# Interfaces.net
KiCad netlist of a schematic drawn in Altium Designer
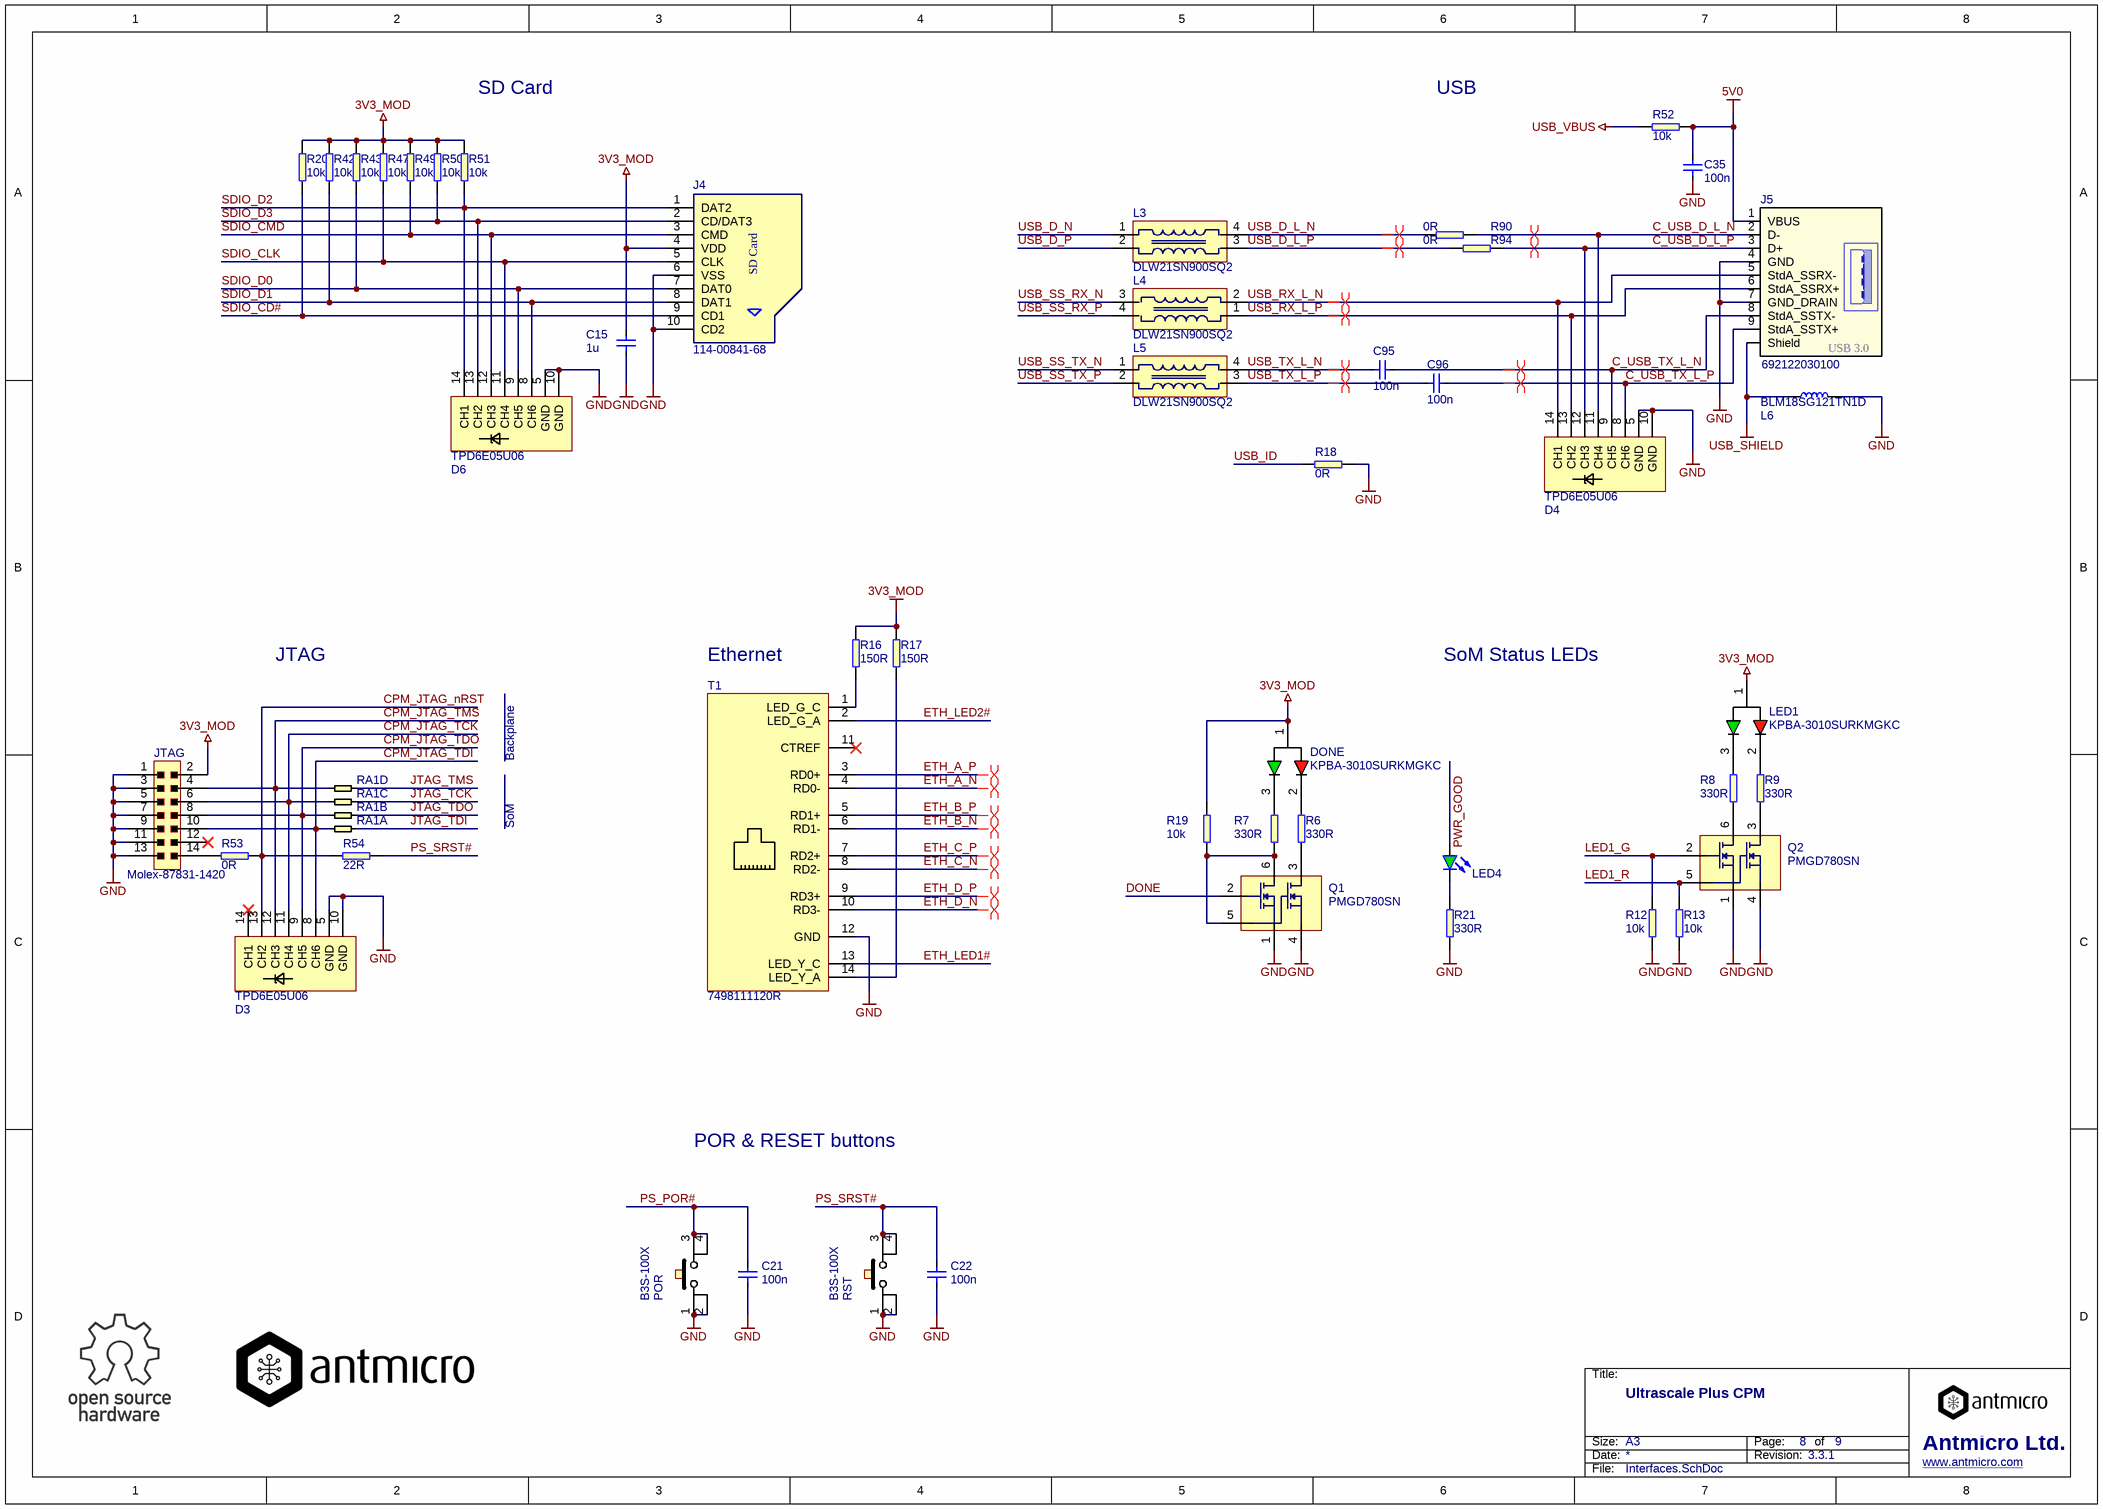
[diagram p0: Interfaces.SchDoc]

(export (version "E")
  (design (tool "Eeschema 10.0.6"))
  (components
    (comp (ref "C15")
      (value "1u")
      (footprint "0603")
      (description "MLCC SMT Capacitor 1uF 0603")
      (fields (field (name "PART NUMBER") "C_1u_0603") (field (name "MANUFACTURER") "MULTICOMP"))
      (libsource (lib "") (part "C_1"))
    )
    (comp (ref "C21")
      (value "100n")
      (footprint "0603")
      (description "MLCC SMT Capacitor 100nF 0603")
      (fields (field (name "PART NUMBER") "C_100n_0603") (field (name "MANUFACTURER") "WALSIN"))
      (libsource (lib "") (part "C_1"))
    )
    (comp (ref "C22")
      (value "100n")
      (footprint "0603")
      (description "MLCC SMT Capacitor 100nF 0603")
      (fields (field (name "PART NUMBER") "C_100n_0603") (field (name "MANUFACTURER") "WALSIN"))
      (libsource (lib "") (part "C_1"))
    )
    (comp (ref "C35")
      (value "100n")
      (footprint "0402")
      (description "MLCC SMT Capacitor 100nF 0402")
      (fields (field (name "PART NUMBER") "C_100n_0402") (field (name "MANUFACTURER") "MULTICOMP"))
      (libsource (lib "US-Plus-CPM") (part "C"))
    )
    (comp (ref "C95")
      (value "100n")
      (footprint "0402")
      (description "MLCC SMT Capacitor 100nF 0402")
      (fields (field (name "PART NUMBER") "C_100n_0402") (field (name "MANUFACTURER") "MULTICOMP"))
      (libsource (lib "US-Plus-CPM") (part "C"))
    )
    (comp (ref "C96")
      (value "100n")
      (footprint "0402")
      (description "MLCC SMT Capacitor 100nF 0402")
      (fields (field (name "PART NUMBER") "C_100n_0402") (field (name "MANUFACTURER") "MULTICOMP"))
      (libsource (lib "US-Plus-CPM") (part "C"))
    )
    (comp (ref "D3")
      (value "TPD6E05U06")
      (footprint "TPD6E05U06_PASS")
      (description "ESD Suppressors 6-CH Pass through layout")
      (fields
        (field (name "PART NUMBER") "TPD6E05U06_PASS")
        (field (name "MANUFACTURER") "Texas Instruments")
      )
      (libsource (lib "US-Plus-CPM") (part "TPD6E05U06"))
    )
    (comp (ref "D4")
      (value "TPD6E05U06")
      (footprint "TPD6E05U06_PASS")
      (description "ESD Suppressors 6-CH Pass through layout")
      (fields
        (field (name "PART NUMBER") "TPD6E05U06_PASS")
        (field (name "MANUFACTURER") "Texas Instruments")
      )
      (libsource (lib "US-Plus-CPM") (part "TPD6E05U06"))
    )
    (comp (ref "D6")
      (value "TPD6E05U06")
      (footprint "TPD6E05U06_PASS")
      (description "ESD Suppressors 6-CH Pass through layout")
      (fields
        (field (name "PART NUMBER") "TPD6E05U06_PASS")
        (field (name "MANUFACTURER") "Texas Instruments")
      )
      (libsource (lib "US-Plus-CPM") (part "TPD6E05U06"))
    )
    (comp (ref "DONE")
      (value "KPBA-3010SURKMGKC")
      (footprint "3010SURKMGKC")
      (description "LED SMD 1104 red/green 3x1mm 140° Lens: transparent")
      (fields (field (name "MANUFACTURER") "Kingbright"))
      (libsource (lib "US-Plus-CPM") (part "3010SURKMGKC"))
    )
    (comp (ref "J4")
      (value "114-00841-68")
      (footprint "114-00841-68")
      (description "Micro SD card holder")
      (fields
        (field (name "PART NUMBER") "AMP-114-00841-68")
        (field (name "MANUFACTURER") "AMPHENOL COMMERCIAL PRODUCTS")
      )
      (libsource (lib "US-Plus-CPM") (part "Micro_SD"))
    )
    (comp (ref "J5")
      (value "692122030100")
      (footprint "WE_692122030100")
      (fields (field (name "PART NUMBER") "WE_692122030100") (field (name "MANUFACTURER") "WURTH ELEKTRONIK"))
      (libsource (lib "US-Plus-CPM") (part "WE_692122030100"))
    )
    (comp (ref "JTAG")
      (value "Molex-87831-1420")
      (footprint "CON-Molex-87831-1420")
      (description "HEADER, SQUARE PIN, M/GRID, 14WAY")
      (fields (field (name "PART NUMBER") "CON-Molex-87831-1420") (field (name "MANUFACTURER") "MOLEX"))
      (libsource (lib "US-Plus-CPM") (part "CON-Molex-87831-1420"))
    )
    (comp (ref "L3")
      (value "DLW21SN900SQ2")
      (footprint "DLW21SN900SQ2")
      (description "Common mode choke")
      (fields (field (name "MANUFACTURER") "MURATA") (field (name "MPN") "DLW21SN900SQ2L"))
      (libsource (lib "") (part "DLW21SN900SQ2_1"))
    )
    (comp (ref "L4")
      (value "DLW21SN900SQ2")
      (footprint "DLW21SN900SQ2")
      (description "Common mode choke")
      (fields (field (name "MANUFACTURER") "MURATA") (field (name "MPN") "DLW21SN900SQ2L"))
      (libsource (lib "US-Plus-CPM") (part "DLW21SN900SQ2"))
    )
    (comp (ref "L5")
      (value "DLW21SN900SQ2")
      (footprint "DLW21SN900SQ2")
      (description "Common mode choke")
      (fields (field (name "MANUFACTURER") "MURATA") (field (name "MPN") "DLW21SN900SQ2L"))
      (libsource (lib "") (part "DLW21SN900SQ2_1"))
    )
    (comp (ref "L6")
      (value "BLM18SG121TN1D")
      (footprint "0603")
      (description "FERRITE BEAD, 0.025OHM, 3A, 0603")
      (fields (field (name "MANUFACTURER") "MURATA"))
      (libsource (lib "US-Plus-CPM") (part "Inductor SMT"))
    )
    (comp (ref "LED1")
      (value "KPBA-3010SURKMGKC")
      (footprint "3010SURKMGKC")
      (description "LED SMD 1104 red/green 3x1mm 140° Lens: transparent")
      (fields (field (name "MANUFACTURER") "Kingbright"))
      (libsource (lib "US-Plus-CPM") (part "3010SURKMGKC"))
    )
    (comp (ref "LED4")
      (value "KPT-1608SGC")
      (footprint "LED0603")
      (description "LED Green 0603 case")
      (fields (field (name "PART NUMBER") "LED_G") (field (name "MANUFACTURER") "KINGBRIGHT"))
      (libsource (lib "US-Plus-CPM") (part "LED"))
    )
    (comp (ref "POR")
      (value "B3S-100X")
      (footprint "B3S-100X")
      (fields
        (field (name "PART NUMBER") "B3S-100X")
        (field (name "MANUFACTURER") "OMRON")
        (field (name "MPN") "B3S-1002")
      )
      (libsource (lib "US-Plus-CPM") (part "TACTILE_SWITCH"))
    )
    (comp (ref "Q1")
      (value "PMGD780SN")
      (footprint "SOT-363")
      (description "60 V, dual N-channel Trench MOSFET")
      (fields (field (name "MANUFACTURER") "NXP") (field (name "MPN") "PMGD780SN,115"))
      (libsource (lib "US-Plus-CPM") (part "PMGD780SN"))
    )
    (comp (ref "Q2")
      (value "PMGD780SN")
      (footprint "SOT-363")
      (description "60 V, dual N-channel Trench MOSFET")
      (fields (field (name "MANUFACTURER") "NXP") (field (name "MPN") "PMGD780SN,115"))
      (libsource (lib "US-Plus-CPM") (part "PMGD780SN"))
    )
    (comp (ref "R6")
      (value "330R")
      (footprint "0603")
      (description "SMT Resistor 330R 0603")
      (fields (field (name "PART NUMBER") "R_330R_0603") (field (name "MANUFACTURER") "BOURNS"))
      (libsource (lib "") (part "R_2"))
    )
    (comp (ref "R7")
      (value "330R")
      (footprint "0603")
      (description "SMT Resistor 330R 0603")
      (fields (field (name "PART NUMBER") "R_330R_0603") (field (name "MANUFACTURER") "BOURNS"))
      (libsource (lib "") (part "R_2"))
    )
    (comp (ref "R8")
      (value "330R")
      (footprint "0402")
      (description "SMT Resistor 0402")
      (fields (field (name "PART NUMBER") "R_330R_0402") (field (name "MANUFACTURER") "MULTICOMP"))
      (libsource (lib "") (part "R_1"))
    )
    (comp (ref "R9")
      (value "330R")
      (footprint "0402")
      (description "SMT Resistor 0402")
      (fields (field (name "PART NUMBER") "R_330R_0402") (field (name "MANUFACTURER") "MULTICOMP"))
      (libsource (lib "") (part "R_1"))
    )
    (comp (ref "R12")
      (value "10k")
      (footprint "0402")
      (description "SMT Resistor 0402")
      (fields (field (name "PART NUMBER") "R_10k_0402") (field (name "MANUFACTURER") "MULTICOMP"))
      (libsource (lib "") (part "R_1"))
    )
    (comp (ref "R13")
      (value "10k")
      (footprint "0402")
      (description "SMT Resistor 0402")
      (fields (field (name "PART NUMBER") "R_10k_0402") (field (name "MANUFACTURER") "MULTICOMP"))
      (libsource (lib "") (part "R_1"))
    )
    (comp (ref "R16")
      (value "150R")
      (footprint "0603")
      (description "SMT Resistor 150R 0603")
      (fields (field (name "PART NUMBER") "R_150R_0603") (field (name "MANUFACTURER") "MULTICOMP"))
      (libsource (lib "") (part "R_1"))
    )
    (comp (ref "R17")
      (value "150R")
      (footprint "0603")
      (description "SMT Resistor 150R 0603")
      (fields (field (name "PART NUMBER") "R_150R_0603") (field (name "MANUFACTURER") "MULTICOMP"))
      (libsource (lib "") (part "R_1"))
    )
    (comp (ref "R18")
      (value "0R")
      (footprint "0603")
      (description "SMT Resistor 0R 0603")
      (fields (field (name "PART NUMBER") "R_0R_0603") (field (name "MANUFACTURER") "BOURNS"))
      (libsource (lib "US-Plus-CPM") (part "R"))
    )
    (comp (ref "R19")
      (value "10k")
      (footprint "0603")
      (description "SMT Resistor 10k 0603")
      (fields (field (name "PART NUMBER") "R_10k_0603") (field (name "MANUFACTURER") "BOURNS"))
      (libsource (lib "") (part "R_1"))
    )
    (comp (ref "R20")
      (value "10k")
      (footprint "0402")
      (description "SMT Resistor 0402")
      (fields (field (name "PART NUMBER") "R_10k_0402") (field (name "MANUFACTURER") "MULTICOMP"))
      (libsource (lib "") (part "R_1"))
    )
    (comp (ref "R21")
      (value "330R")
      (footprint "0603")
      (description "SMT Resistor 330R 0603")
      (fields (field (name "PART NUMBER") "R_330R_0603") (field (name "MANUFACTURER") "BOURNS"))
      (libsource (lib "") (part "R_2"))
    )
    (comp (ref "R42")
      (value "10k")
      (footprint "0402")
      (description "SMT Resistor 0402")
      (fields (field (name "PART NUMBER") "R_10k_0402") (field (name "MANUFACTURER") "MULTICOMP"))
      (libsource (lib "") (part "R_1"))
    )
    (comp (ref "R43")
      (value "10k")
      (footprint "0402")
      (description "SMT Resistor 0402")
      (fields (field (name "PART NUMBER") "R_10k_0402") (field (name "MANUFACTURER") "MULTICOMP"))
      (libsource (lib "") (part "R_1"))
    )
    (comp (ref "R47")
      (value "10k")
      (footprint "0402")
      (description "SMT Resistor 0402")
      (fields (field (name "PART NUMBER") "R_10k_0402") (field (name "MANUFACTURER") "MULTICOMP"))
      (libsource (lib "") (part "R_1"))
    )
    (comp (ref "R49")
      (value "10k")
      (footprint "0402")
      (description "SMT Resistor 0402")
      (fields (field (name "PART NUMBER") "R_10k_0402") (field (name "MANUFACTURER") "MULTICOMP"))
      (libsource (lib "") (part "R_1"))
    )
    (comp (ref "R50")
      (value "10k")
      (footprint "0402")
      (description "SMT Resistor 0402")
      (fields (field (name "PART NUMBER") "R_10k_0402") (field (name "MANUFACTURER") "MULTICOMP"))
      (libsource (lib "") (part "R_1"))
    )
    (comp (ref "R51")
      (value "10k")
      (footprint "0402")
      (description "SMT Resistor 0402")
      (fields (field (name "PART NUMBER") "R_10k_0402") (field (name "MANUFACTURER") "MULTICOMP"))
      (libsource (lib "") (part "R_1"))
    )
    (comp (ref "R52")
      (value "10k")
      (footprint "0603")
      (description "SMT Resistor 10k 0603")
      (fields (field (name "PART NUMBER") "R_10k_0603") (field (name "MANUFACTURER") "BOURNS"))
      (libsource (lib "US-Plus-CPM") (part "R"))
    )
    (comp (ref "R53")
      (value "0R")
      (footprint "0603")
      (description "SMT Resistor 0R 0603")
      (fields (field (name "PART NUMBER") "R_0R_0603") (field (name "MANUFACTURER") "BOURNS"))
      (libsource (lib "US-Plus-CPM") (part "R"))
    )
    (comp (ref "R54")
      (value "22R")
      (footprint "0603")
      (description "SMT Resistor 22R 0603")
      (fields (field (name "PART NUMBER") "R_22R_0603") (field (name "MANUFACTURER") "BOURNS"))
      (libsource (lib "US-Plus-CPM") (part "R"))
    )
    (comp (ref "R90")
      (value "0R")
      (footprint "0402")
      (description "SMT Resistor 0402")
      (fields (field (name "PART NUMBER") "R_0R_0402") (field (name "MANUFACTURER") "MULTICOMP"))
      (libsource (lib "US-Plus-CPM") (part "R"))
    )
    (comp (ref "R94")
      (value "0R")
      (footprint "0402")
      (description "SMT Resistor 0402")
      (fields (field (name "PART NUMBER") "R_0R_0402") (field (name "MANUFACTURER") "MULTICOMP"))
      (libsource (lib "US-Plus-CPM") (part "R"))
    )
    (comp (ref "RA1")
      (value "22R")
      (footprint "RA_1206")
      (description "YAGEO (PHYCOMP)  TC164-JR-0722RL  RESISTOR ARRAY, ARC241 1206 22R")
      (fields
        (field (name "PART NUMBER") "RA-22R-63mW-5%-1206")
        (field (name "MANUFACTURER") "YAGEO (PHYCOMP)")
      )
      (libsource (lib "US-Plus-CPM") (part "Res_array_4"))
    )
    (comp (ref "RST")
      (value "B3S-100X")
      (footprint "B3S-100X")
      (fields
        (field (name "PART NUMBER") "B3S-100X")
        (field (name "MANUFACTURER") "OMRON")
        (field (name "MPN") "B3S-1002")
      )
      (libsource (lib "US-Plus-CPM") (part "TACTILE_SWITCH"))
    )
    (comp (ref "T1")
      (value "7498111120R")
      (footprint "7498111120R")
      (description "LAN transformer 1000Base-T")
      (fields (field (name "PART NUMBER") "WE_7498111120R") (field (name "MANUFACTURER") "WURTH ELEKTRONIK"))
      (libsource (lib "US-Plus-CPM") (part "WE_7498111120R"))
    )
  )
  (nets
    (net (code "1") (name "/CPM_JTAG_TCK") (class "Default")
      (node (ref "D3") (pin "11") (pinfunction "CH4_11") (pintype "passive"))
      (node (ref "JTAG") (pin "6") (pinfunction "6_6") (pintype "passive"))
      (node (ref "RA1") (pin "3") (pinfunction "3_3") (pintype "passive"))
    )
    (net (code "2") (name "/CPM_JTAG_TDI") (class "Default")
      (node (ref "D3") (pin "8") (pinfunction "CH6_8") (pintype "passive"))
      (node (ref "JTAG") (pin "10") (pinfunction "10_10") (pintype "passive"))
      (node (ref "RA1") (pin "1") (pinfunction "1_1") (pintype "passive"))
    )
    (net (code "3") (name "/CPM_JTAG_TDO") (class "Default")
      (node (ref "D3") (pin "9") (pinfunction "CH5_9") (pintype "passive"))
      (node (ref "JTAG") (pin "8") (pinfunction "8_8") (pintype "passive"))
      (node (ref "RA1") (pin "2") (pinfunction "2_2") (pintype "passive"))
    )
    (net (code "4") (name "/CPM_JTAG_TMS") (class "Default")
      (node (ref "D3") (pin "12") (pinfunction "CH3_12") (pintype "passive"))
      (node (ref "JTAG") (pin "4") (pinfunction "4_4") (pintype "passive"))
      (node (ref "RA1") (pin "4") (pinfunction "4_4") (pintype "passive"))
    )
    (net (code "5") (name "/CPM_JTAG_nRST") (class "Default")
      (node (ref "D3") (pin "13") (pinfunction "CH2_13") (pintype "passive"))
      (node (ref "R53") (pin "2") (pintype "passive"))
      (node (ref "R54") (pin "1") (pintype "passive"))
    )
    (net (code "6") (name "/C_USB_D_L_N") (class "Default")
      (node (ref "D4") (pin "11") (pinfunction "CH4_11") (pintype "passive"))
      (node (ref "J5") (pin "2") (pinfunction "D-_2") (pintype "passive"))
      (node (ref "R90") (pin "2") (pintype "passive"))
    )
    (net (code "7") (name "/C_USB_D_L_P") (class "Default")
      (node (ref "D4") (pin "12") (pinfunction "CH3_12") (pintype "passive"))
      (node (ref "J5") (pin "3") (pinfunction "D+_3") (pintype "passive"))
      (node (ref "R94") (pin "2") (pintype "passive"))
    )
    (net (code "8") (name "/C_USB_TX_L_N") (class "Default")
      (node (ref "C95") (pin "2") (pinfunction "2_2") (pintype "passive"))
      (node (ref "D4") (pin "9") (pinfunction "CH5_9") (pintype "passive"))
      (node (ref "J5") (pin "8") (pinfunction "StdA_SSTX-_8") (pintype "passive"))
    )
    (net (code "9") (name "/C_USB_TX_L_P") (class "Default")
      (node (ref "C96") (pin "2") (pinfunction "2_2") (pintype "passive"))
      (node (ref "D4") (pin "8") (pinfunction "CH6_8") (pintype "passive"))
      (node (ref "J5") (pin "9") (pinfunction "StdA_SSTX+_9") (pintype "passive"))
    )
    (net (code "10") (name "/DONE") (class "Default")
      (node (ref "Q1") (pin "2") (pinfunction "G1_2") (pintype "passive"))
    )
    (net (code "11") (name "/ETH_A_N") (class "Default")
      (node (ref "T1") (pin "4") (pinfunction "RD0-_4") (pintype "passive"))
    )
    (net (code "12") (name "/ETH_A_P") (class "Default")
      (node (ref "T1") (pin "3") (pinfunction "RD0+_3") (pintype "passive"))
    )
    (net (code "13") (name "/ETH_B_N") (class "Default")
      (node (ref "T1") (pin "6") (pinfunction "RD1-_6") (pintype "passive"))
    )
    (net (code "14") (name "/ETH_B_P") (class "Default")
      (node (ref "T1") (pin "5") (pinfunction "RD1+_5") (pintype "passive"))
    )
    (net (code "15") (name "/ETH_C_N") (class "Default")
      (node (ref "T1") (pin "8") (pinfunction "RD2-_8") (pintype "passive"))
    )
    (net (code "16") (name "/ETH_C_P") (class "Default")
      (node (ref "T1") (pin "7") (pinfunction "RD2+_7") (pintype "passive"))
    )
    (net (code "17") (name "/ETH_D_N") (class "Default")
      (node (ref "T1") (pin "10") (pinfunction "RD3-_10") (pintype "passive"))
    )
    (net (code "18") (name "/ETH_D_P") (class "Default")
      (node (ref "T1") (pin "9") (pinfunction "RD3+_9") (pintype "passive"))
    )
    (net (code "19") (name "/ETH_LED1#") (class "Default")
      (node (ref "T1") (pin "13") (pinfunction "LED_Y_C_13") (pintype "passive"))
    )
    (net (code "20") (name "/ETH_LED2#") (class "Default")
      (node (ref "T1") (pin "2") (pinfunction "LED_G_A_2") (pintype "passive"))
    )
    (net (code "21") (name "/JTAG_TCK") (class "Default")
      (node (ref "RA1") (pin "7") (pinfunction "7_7") (pintype "passive"))
    )
    (net (code "22") (name "/JTAG_TDI") (class "Default")
      (node (ref "RA1") (pin "5") (pinfunction "5_5") (pintype "passive"))
    )
    (net (code "23") (name "/JTAG_TDO") (class "Default")
      (node (ref "RA1") (pin "6") (pinfunction "6_6") (pintype "passive"))
    )
    (net (code "24") (name "/JTAG_TMS") (class "Default")
      (node (ref "RA1") (pin "8") (pinfunction "8_8") (pintype "passive"))
    )
    (net (code "25") (name "/LED1_G") (class "Default")
      (node (ref "Q2") (pin "2") (pinfunction "G1_2") (pintype "passive"))
      (node (ref "R12") (pin "2") (pintype "passive"))
    )
    (net (code "26") (name "/LED1_R") (class "Default")
      (node (ref "Q2") (pin "5") (pinfunction "G2_5") (pintype "passive"))
      (node (ref "R13") (pin "2") (pintype "passive"))
    )
    (net (code "27") (name "/PS_POR#") (class "Default")
      (node (ref "C21") (pin "2") (pinfunction "2_2") (pintype "passive"))
      (node (ref "POR") (pin "3") (pinfunction "3_3") (pintype "passive"))
      (node (ref "POR") (pin "4") (pinfunction "4_4") (pintype "passive"))
    )
    (net (code "28") (name "/PS_SRST#") (class "Default")
      (node (ref "C22") (pin "2") (pinfunction "2_2") (pintype "passive"))
      (node (ref "R54") (pin "2") (pintype "passive"))
      (node (ref "RST") (pin "3") (pinfunction "3_3") (pintype "passive"))
      (node (ref "RST") (pin "4") (pinfunction "4_4") (pintype "passive"))
    )
    (net (code "29") (name "/PWR_GOOD") (class "Default")
      (node (ref "LED4") (pin "A") (pinfunction "A_A") (pintype "passive"))
    )
    (net (code "30") (name "/SDIO_CD#") (class "Default")
      (node (ref "J4") (pin "9") (pinfunction "CD1_9") (pintype "passive"))
      (node (ref "R20") (pin "1") (pintype "passive"))
    )
    (net (code "31") (name "/SDIO_CLK") (class "Default")
      (node (ref "D6") (pin "11") (pinfunction "CH4_11") (pintype "passive"))
      (node (ref "J4") (pin "5") (pinfunction "CLK_5") (pintype "passive"))
      (node (ref "R47") (pin "1") (pintype "passive"))
    )
    (net (code "32") (name "/SDIO_CMD") (class "Default")
      (node (ref "D6") (pin "12") (pinfunction "CH3_12") (pintype "passive"))
      (node (ref "J4") (pin "3") (pinfunction "CMD_3") (pintype "passive"))
      (node (ref "R49") (pin "1") (pintype "passive"))
    )
    (net (code "33") (name "/SDIO_D0") (class "Default")
      (node (ref "D6") (pin "9") (pinfunction "CH5_9") (pintype "passive"))
      (node (ref "J4") (pin "7") (pinfunction "DAT0_7") (pintype "passive"))
      (node (ref "R43") (pin "1") (pintype "passive"))
    )
    (net (code "34") (name "/SDIO_D1") (class "Default")
      (node (ref "D6") (pin "8") (pinfunction "CH6_8") (pintype "passive"))
      (node (ref "J4") (pin "8") (pinfunction "DAT1_8") (pintype "passive"))
      (node (ref "R42") (pin "1") (pintype "passive"))
    )
    (net (code "35") (name "/SDIO_D2") (class "Default")
      (node (ref "D6") (pin "14") (pinfunction "CH1_14") (pintype "passive"))
      (node (ref "J4") (pin "1") (pinfunction "DAT2_1") (pintype "passive"))
      (node (ref "R51") (pin "1") (pintype "passive"))
    )
    (net (code "36") (name "/SDIO_D3") (class "Default")
      (node (ref "D6") (pin "13") (pinfunction "CH2_13") (pintype "passive"))
      (node (ref "J4") (pin "2") (pinfunction "CD/DAT3_2") (pintype "passive"))
      (node (ref "R50") (pin "1") (pintype "passive"))
    )
    (net (code "37") (name "/USB_D_L_N") (class "Default")
      (node (ref "L3") (pin "4") (pinfunction "4_4") (pintype "passive"))
      (node (ref "R90") (pin "1") (pintype "passive"))
    )
    (net (code "38") (name "/USB_D_L_P") (class "Default")
      (node (ref "L3") (pin "3") (pinfunction "3_3") (pintype "passive"))
      (node (ref "R94") (pin "1") (pintype "passive"))
    )
    (net (code "39") (name "/USB_D_N") (class "Default")
      (node (ref "L3") (pin "1") (pinfunction "1_1") (pintype "passive"))
    )
    (net (code "40") (name "/USB_D_P") (class "Default")
      (node (ref "L3") (pin "2") (pinfunction "2_2") (pintype "passive"))
    )
    (net (code "41") (name "/USB_ID") (class "Default") (node (ref "R18") (pin "1") (pintype "passive")))
    (net (code "42") (name "/USB_RX_L_N") (class "Default")
      (node (ref "D4") (pin "14") (pinfunction "CH1_14") (pintype "passive"))
      (node (ref "J5") (pin "5") (pinfunction "StdA_SSRX-_5") (pintype "passive"))
      (node (ref "L4") (pin "2") (pinfunction "2_2") (pintype "passive"))
    )
    (net (code "43") (name "/USB_RX_L_P") (class "Default")
      (node (ref "D4") (pin "13") (pinfunction "CH2_13") (pintype "passive"))
      (node (ref "J5") (pin "6") (pinfunction "StdA_SSRX+_6") (pintype "passive"))
      (node (ref "L4") (pin "1") (pinfunction "1_1") (pintype "passive"))
    )
    (net (code "44") (name "/USB_SS_RX_N") (class "Default")
      (node (ref "L4") (pin "3") (pinfunction "3_3") (pintype "passive"))
    )
    (net (code "45") (name "/USB_SS_RX_P") (class "Default")
      (node (ref "L4") (pin "4") (pinfunction "4_4") (pintype "passive"))
    )
    (net (code "46") (name "/USB_SS_TX_N") (class "Default")
      (node (ref "L5") (pin "1") (pinfunction "1_1") (pintype "passive"))
    )
    (net (code "47") (name "/USB_SS_TX_P") (class "Default")
      (node (ref "L5") (pin "2") (pinfunction "2_2") (pintype "passive"))
    )
    (net (code "48") (name "/USB_TX_L_N") (class "Default")
      (node (ref "C95") (pin "1") (pinfunction "1_1") (pintype "passive"))
      (node (ref "L5") (pin "4") (pinfunction "4_4") (pintype "passive"))
    )
    (net (code "49") (name "/USB_TX_L_P") (class "Default")
      (node (ref "C96") (pin "1") (pinfunction "1_1") (pintype "passive"))
      (node (ref "L5") (pin "3") (pinfunction "3_3") (pintype "passive"))
    )
    (net (code "50") (name "3V3_MOD") (class "Default")
      (node (ref "C15") (pin "2") (pinfunction "2_2") (pintype "passive"))
      (node (ref "DONE") (pin "1") (pinfunction "CA_1") (pintype "passive"))
      (node (ref "J4") (pin "4") (pinfunction "VDD_4") (pintype "passive"))
      (node (ref "JTAG") (pin "2") (pinfunction "2_2") (pintype "passive"))
      (node (ref "LED1") (pin "1") (pinfunction "CA_1") (pintype "passive"))
      (node (ref "R16") (pin "2") (pintype "passive"))
      (node (ref "R17") (pin "2") (pintype "passive"))
      (node (ref "R19") (pin "2") (pintype "passive"))
      (node (ref "R20") (pin "2") (pintype "passive"))
      (node (ref "R42") (pin "2") (pintype "passive"))
      (node (ref "R43") (pin "2") (pintype "passive"))
      (node (ref "R47") (pin "2") (pintype "passive"))
      (node (ref "R49") (pin "2") (pintype "passive"))
      (node (ref "R50") (pin "2") (pintype "passive"))
      (node (ref "R51") (pin "2") (pintype "passive"))
    )
    (net (code "51") (name "5V0") (class "Default")
      (node (ref "C35") (pin "2") (pinfunction "2_2") (pintype "passive"))
      (node (ref "J5") (pin "1") (pinfunction "VBUS_1") (pintype "passive"))
      (node (ref "R52") (pin "2") (pintype "passive"))
    )
    (net (code "52") (name "GND") (class "Default")
      (node (ref "C15") (pin "1") (pinfunction "1_1") (pintype "passive"))
      (node (ref "C21") (pin "1") (pinfunction "1_1") (pintype "passive"))
      (node (ref "C22") (pin "1") (pinfunction "1_1") (pintype "passive"))
      (node (ref "C35") (pin "1") (pinfunction "1_1") (pintype "passive"))
      (node (ref "D3") (pin "10") (pinfunction "GND_10") (pintype "passive"))
      (node (ref "D3") (pin "5") (pinfunction "GND_5") (pintype "passive"))
      (node (ref "D4") (pin "10") (pinfunction "GND_10") (pintype "passive"))
      (node (ref "D4") (pin "5") (pinfunction "GND_5") (pintype "passive"))
      (node (ref "D6") (pin "10") (pinfunction "GND_10") (pintype "passive"))
      (node (ref "D6") (pin "5") (pinfunction "GND_5") (pintype "passive"))
      (node (ref "J4") (pin "10") (pinfunction "CD2_10") (pintype "passive"))
      (node (ref "J4") (pin "6") (pinfunction "VSS_6") (pintype "passive"))
      (node (ref "J5") (pin "4") (pinfunction "GND_4") (pintype "passive"))
      (node (ref "J5") (pin "7") (pinfunction "GND_DRAIN_7") (pintype "passive"))
      (node (ref "JTAG") (pin "1") (pinfunction "1_1") (pintype "passive"))
      (node (ref "JTAG") (pin "11") (pinfunction "11_11") (pintype "passive"))
      (node (ref "JTAG") (pin "13") (pinfunction "13_13") (pintype "passive"))
      (node (ref "JTAG") (pin "3") (pinfunction "3_3") (pintype "passive"))
      (node (ref "JTAG") (pin "5") (pinfunction "5_5") (pintype "passive"))
      (node (ref "JTAG") (pin "7") (pinfunction "7_7") (pintype "passive"))
      (node (ref "JTAG") (pin "9") (pinfunction "9_9") (pintype "passive"))
      (node (ref "L6") (pin "2") (pintype "passive"))
      (node (ref "POR") (pin "1") (pinfunction "1_1") (pintype "passive"))
      (node (ref "POR") (pin "2") (pinfunction "2_2") (pintype "passive"))
      (node (ref "Q1") (pin "1") (pinfunction "S1_1") (pintype "passive"))
      (node (ref "Q1") (pin "4") (pinfunction "S2_4") (pintype "passive"))
      (node (ref "Q2") (pin "1") (pinfunction "S1_1") (pintype "passive"))
      (node (ref "Q2") (pin "4") (pinfunction "S2_4") (pintype "passive"))
      (node (ref "R12") (pin "1") (pintype "passive"))
      (node (ref "R13") (pin "1") (pintype "passive"))
      (node (ref "R18") (pin "2") (pintype "passive"))
      (node (ref "R21") (pin "2") (pintype "passive"))
      (node (ref "RST") (pin "1") (pinfunction "1_1") (pintype "passive"))
      (node (ref "RST") (pin "2") (pinfunction "2_2") (pintype "passive"))
      (node (ref "T1") (pin "12") (pinfunction "GND_12") (pintype "passive"))
    )
    (net (code "53") (name "Net-(DONE-G_K)") (class "Default")
      (node (ref "DONE") (pin "3") (pinfunction "G_K_3") (pintype "passive"))
      (node (ref "R7") (pin "1") (pintype "passive"))
    )
    (net (code "54") (name "Net-(DONE-R_K)") (class "Default")
      (node (ref "DONE") (pin "2") (pinfunction "R_K_2") (pintype "passive"))
      (node (ref "R6") (pin "1") (pintype "passive"))
    )
    (net (code "55") (name "Net-(JTAG-Pad14)") (class "Default")
      (node (ref "JTAG") (pin "14") (pinfunction "14_14") (pintype "passive"))
      (node (ref "R53") (pin "1") (pintype "passive"))
    )
    (net (code "56") (name "Net-(LED1-G_K)") (class "Default")
      (node (ref "LED1") (pin "3") (pinfunction "G_K_3") (pintype "passive"))
      (node (ref "R8") (pin "2") (pintype "passive"))
    )
    (net (code "57") (name "Net-(LED1-R_K)") (class "Default")
      (node (ref "LED1") (pin "2") (pinfunction "R_K_2") (pintype "passive"))
      (node (ref "R9") (pin "2") (pintype "passive"))
    )
    (net (code "58") (name "Net-(LED4-PadK)") (class "Default")
      (node (ref "LED4") (pin "K") (pinfunction "K_K") (pintype "passive"))
      (node (ref "R21") (pin "1") (pintype "passive"))
    )
    (net (code "59") (name "Net-(Q1-D1)") (class "Default")
      (node (ref "Q1") (pin "5") (pinfunction "G2_5") (pintype "passive"))
      (node (ref "Q1") (pin "6") (pinfunction "D1_6") (pintype "passive"))
      (node (ref "R19") (pin "1") (pintype "passive"))
      (node (ref "R7") (pin "2") (pintype "passive"))
    )
    (net (code "60") (name "Net-(Q1-D2)") (class "Default")
      (node (ref "Q1") (pin "3") (pinfunction "D2_3") (pintype "passive"))
      (node (ref "R6") (pin "2") (pintype "passive"))
    )
    (net (code "61") (name "Net-(Q2-D1)") (class "Default")
      (node (ref "Q2") (pin "6") (pinfunction "D1_6") (pintype "passive"))
      (node (ref "R8") (pin "1") (pintype "passive"))
    )
    (net (code "62") (name "Net-(Q2-D2)") (class "Default")
      (node (ref "Q2") (pin "3") (pinfunction "D2_3") (pintype "passive"))
      (node (ref "R9") (pin "1") (pintype "passive"))
    )
    (net (code "63") (name "Net-(T1-LED_G_C)") (class "Default")
      (node (ref "R16") (pin "1") (pintype "passive"))
      (node (ref "T1") (pin "1") (pinfunction "LED_G_C_1") (pintype "passive"))
    )
    (net (code "64") (name "Net-(T1-LED_Y_A)") (class "Default")
      (node (ref "R17") (pin "1") (pintype "passive"))
      (node (ref "T1") (pin "14") (pinfunction "LED_Y_A_14") (pintype "passive"))
    )
    (net (code "65") (name "USB_SHIELD") (class "Default")
      (node (ref "J5") (pin "Z1") (pinfunction "Shield_Z1") (pintype "passive"))
      (node (ref "L6") (pin "1") (pintype "passive"))
    )
    (net (code "66") (name "USB_VBUS") (class "Default") (node (ref "R52") (pin "1") (pintype "passive")))
    (net (code "67") (name "unconnected-(D3-CH1-Pad14)") (class "Default")
      (node (ref "D3") (pin "14") (pinfunction "CH1_14") (pintype "passive+no_connect"))
    )
    (net (code "68") (name "unconnected-(JTAG-Pad12)") (class "Default")
      (node (ref "JTAG") (pin "12") (pinfunction "12_12") (pintype "passive+no_connect"))
    )
    (net (code "69") (name "unconnected-(T1-CTREF-Pad11)") (class "Default")
      (node (ref "T1") (pin "11") (pinfunction "CTREF_11") (pintype "passive+no_connect"))
    )
  )
)
